# AVR.net
KiCad netlist of a schematic drawn in Altium Designer
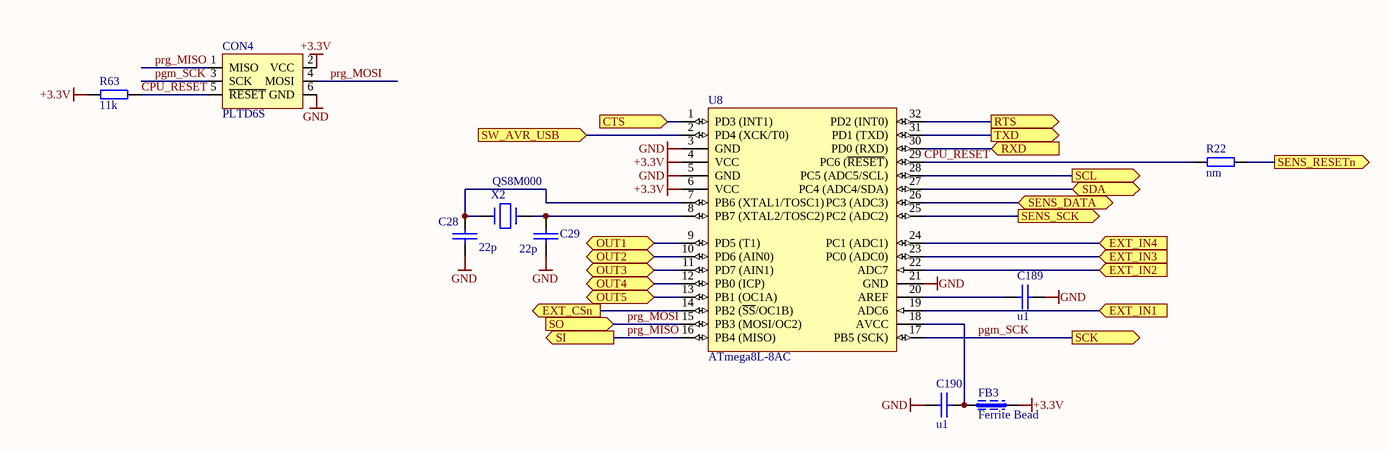
[diagram p0: AVR.SchDoc]

(export (version "E")
  (design (tool "Eeschema 10.0.6"))
  (components
    (comp (ref "C28")
      (value "22p")
      (footprint "0603")
      (description "Capacitor SMD")
      (libsource (lib "LIBRARY_SCH") (part "CAP_SMD"))
    )
    (comp (ref "C29")
      (value "22p")
      (footprint "0603")
      (description "Capacitor SMD")
      (libsource (lib "LIBRARY_SCH") (part "CAP_SMD"))
    )
    (comp (ref "C189")
      (value "u1")
      (footprint "0603")
      (description "Capacitor SMD")
      (libsource (lib "LIBRARY_SCH") (part "CAP_SMD"))
    )
    (comp (ref "C190")
      (value "u1")
      (footprint "0603")
      (description "Capacitor SMD")
      (libsource (lib "LIBRARY_SCH") (part "CAP_SMD"))
    )
    (comp (ref "CON4") (value "PLTD6S") (footprint "PLTD6S") (libsource (lib "LIBRARY_SCH") (part "CON_ISP")))
    (comp (ref "FB3")
      (value "Ferrite Bead")
      (footprint "0603")
      (description "ferrite bead")
      (libsource (lib "*") (part "L_FERRITE_BEAD"))
    )
    (comp (ref "R22")
      (value "nm")
      (footprint "0603")
      (description "SMD Resistor")
      (libsource (lib "LIBRARY_SCH") (part "RES_SMD"))
    )
    (comp (ref "R63")
      (value "11k")
      (footprint "0603")
      (description "SMD Resistor")
      (libsource (lib "LIBRARY_SCH") (part "RES_SMD"))
    )
    (comp (ref "U8")
      (value "ATmega8L-8AC")
      (footprint "QFP32a")
      (description "8-Bit AVR Microcontroller with 8K Bytes of In-System Programmable Flash Memory")
      (fields (field (name "PUBLISHER") "Altium Limited"))
      (libsource (lib "LIBRARY_SCH") (part "ATmega8-16AI"))
    )
    (comp (ref "X2")
      (value "QS8M000")
      (footprint "HC-49SM")
      (description "Crystal oscillator")
      (libsource (lib "LIBRARY_SCH") (part "CRYSTAL"))
    )
  )
  (nets
    (net (code "1") (name "+3.3V") (class "Default")
      (node (ref "CON4") (pin "2") (pinfunction "VCC_2") (pintype "passive"))
      (node (ref "FB3") (pin "2") (pinfunction "2_2") (pintype "passive"))
      (node (ref "R63") (pin "2") (pinfunction "2_2") (pintype "passive"))
      (node (ref "U8") (pin "4") (pinfunction "VCC_4") (pintype "power_in"))
      (node (ref "U8") (pin "6") (pinfunction "VCC_6") (pintype "power_in"))
    )
    (net (code "2") (name "/CPU_RESET") (class "Default")
      (node (ref "CON4") (pin "5") (pinfunction "~{RESET}_5") (pintype "passive"))
      (node (ref "R22") (pin "2") (pinfunction "2_2") (pintype "passive"))
      (node (ref "R63") (pin "1") (pinfunction "1_1") (pintype "passive"))
      (node (ref "U8") (pin "29") (pinfunction "PC6_(~{RESET})_29") (pintype "bidirectional"))
    )
    (net (code "3") (name "/CTS") (class "Default")
      (node (ref "U8") (pin "1") (pinfunction "PD3_(INT1)_1") (pintype "bidirectional"))
    )
    (net (code "4") (name "/EXT_CSn") (class "Default")
      (node (ref "U8") (pin "14") (pinfunction "PB2_(~{SS}/OC1B)_14") (pintype "bidirectional"))
    )
    (net (code "5") (name "/EXT_IN1") (class "Default")
      (node (ref "U8") (pin "19") (pinfunction "ADC6_19") (pintype "input"))
    )
    (net (code "6") (name "/EXT_IN2") (class "Default")
      (node (ref "U8") (pin "22") (pinfunction "ADC7_22") (pintype "input"))
    )
    (net (code "7") (name "/EXT_IN3") (class "Default")
      (node (ref "U8") (pin "23") (pinfunction "PC0_(ADC0)_23") (pintype "bidirectional"))
    )
    (net (code "8") (name "/EXT_IN4") (class "Default")
      (node (ref "U8") (pin "24") (pinfunction "PC1_(ADC1)_24") (pintype "bidirectional"))
    )
    (net (code "9") (name "/OUT1") (class "Default")
      (node (ref "U8") (pin "9") (pinfunction "PD5_(T1)_9") (pintype "bidirectional"))
    )
    (net (code "10") (name "/OUT2") (class "Default")
      (node (ref "U8") (pin "10") (pinfunction "PD6_(AIN0)_10") (pintype "bidirectional"))
    )
    (net (code "11") (name "/OUT3") (class "Default")
      (node (ref "U8") (pin "11") (pinfunction "PD7_(AIN1)_11") (pintype "bidirectional"))
    )
    (net (code "12") (name "/OUT4") (class "Default")
      (node (ref "U8") (pin "12") (pinfunction "PB0_(ICP)_12") (pintype "bidirectional"))
    )
    (net (code "13") (name "/OUT5") (class "Default")
      (node (ref "U8") (pin "13") (pinfunction "PB1_(OC1A)_13") (pintype "bidirectional"))
    )
    (net (code "14") (name "/RTS") (class "Default")
      (node (ref "U8") (pin "32") (pinfunction "PD2_(INT0)_32") (pintype "bidirectional"))
    )
    (net (code "15") (name "/RXD") (class "Default")
      (node (ref "U8") (pin "30") (pinfunction "PD0_(RXD)_30") (pintype "bidirectional"))
    )
    (net (code "16") (name "/SCL") (class "Default")
      (node (ref "U8") (pin "28") (pinfunction "PC5_(ADC5/SCL)_28") (pintype "bidirectional"))
    )
    (net (code "17") (name "/SDA") (class "Default")
      (node (ref "U8") (pin "27") (pinfunction "PC4_(ADC4/SDA)_27") (pintype "bidirectional"))
    )
    (net (code "18") (name "/SENS_DATA") (class "Default")
      (node (ref "U8") (pin "26") (pinfunction "PC3_(ADC3)_26") (pintype "bidirectional"))
    )
    (net (code "19") (name "/SENS_RESETn") (class "Default")
      (node (ref "R22") (pin "1") (pinfunction "1_1") (pintype "passive"))
    )
    (net (code "20") (name "/SENS_SCK") (class "Default")
      (node (ref "U8") (pin "25") (pinfunction "PC2_(ADC2)_25") (pintype "bidirectional"))
    )
    (net (code "21") (name "/SW_AVR_USB") (class "Default")
      (node (ref "U8") (pin "2") (pinfunction "PD4_(XCK/T0)_2") (pintype "bidirectional"))
    )
    (net (code "22") (name "/TXD") (class "Default")
      (node (ref "U8") (pin "31") (pinfunction "PD1_(TXD)_31") (pintype "bidirectional"))
    )
    (net (code "23") (name "/pgm_SCK") (class "Default")
      (node (ref "CON4") (pin "3") (pinfunction "SCK_3") (pintype "passive"))
      (node (ref "U8") (pin "17") (pinfunction "PB5_(SCK)_17") (pintype "bidirectional"))
    )
    (net (code "24") (name "/prg_MISO") (class "Default")
      (node (ref "CON4") (pin "1") (pinfunction "MISO_1") (pintype "passive"))
      (node (ref "U8") (pin "16") (pinfunction "PB4_(MISO)_16") (pintype "bidirectional"))
    )
    (net (code "25") (name "/prg_MOSI") (class "Default")
      (node (ref "CON4") (pin "4") (pinfunction "MOSI_4") (pintype "passive"))
      (node (ref "U8") (pin "15") (pinfunction "PB3_(MOSI/OC2)_15") (pintype "bidirectional"))
    )
    (net (code "26") (name "GND") (class "Default")
      (node (ref "C189") (pin "2") (pinfunction "2_2") (pintype "passive"))
      (node (ref "C190") (pin "2") (pinfunction "2_2") (pintype "passive"))
      (node (ref "C28") (pin "1") (pinfunction "1_1") (pintype "passive"))
      (node (ref "C29") (pin "1") (pinfunction "1_1") (pintype "passive"))
      (node (ref "CON4") (pin "6") (pinfunction "GND_6") (pintype "passive"))
      (node (ref "U8") (pin "21") (pinfunction "GND_21") (pintype "power_in"))
      (node (ref "U8") (pin "3") (pinfunction "GND_3") (pintype "power_in"))
      (node (ref "U8") (pin "5") (pinfunction "GND_5") (pintype "power_in"))
    )
    (net (code "27") (name "Net-(U8-AREF)") (class "Default")
      (node (ref "C189") (pin "1") (pinfunction "1_1") (pintype "passive"))
      (node (ref "U8") (pin "20") (pinfunction "AREF_20") (pintype "passive"))
    )
    (net (code "28") (name "Net-(U8-AVCC)") (class "Default")
      (node (ref "C190") (pin "1") (pinfunction "1_1") (pintype "passive"))
      (node (ref "FB3") (pin "1") (pinfunction "1_1") (pintype "passive"))
      (node (ref "U8") (pin "18") (pinfunction "AVCC_18") (pintype "power_in"))
    )
    (net (code "29") (name "Net-(U8-PB6_(XTAL1{slash}TOSC1))") (class "Default")
      (node (ref "C28") (pin "2") (pinfunction "2_2") (pintype "passive"))
      (node (ref "U8") (pin "7") (pinfunction "PB6_(XTAL1/TOSC1)_7") (pintype "bidirectional"))
      (node (ref "X2") (pin "1") (pinfunction "1_1") (pintype "passive"))
    )
    (net (code "30") (name "Net-(U8-PB7_(XTAL2{slash}TOSC2))") (class "Default")
      (node (ref "C29") (pin "2") (pinfunction "2_2") (pintype "passive"))
      (node (ref "U8") (pin "8") (pinfunction "PB7_(XTAL2/TOSC2)_8") (pintype "bidirectional"))
      (node (ref "X2") (pin "2") (pinfunction "2_2") (pintype "passive"))
    )
  )
)
